# bmp180.net
KiCad netlist of a schematic drawn in EAGLE
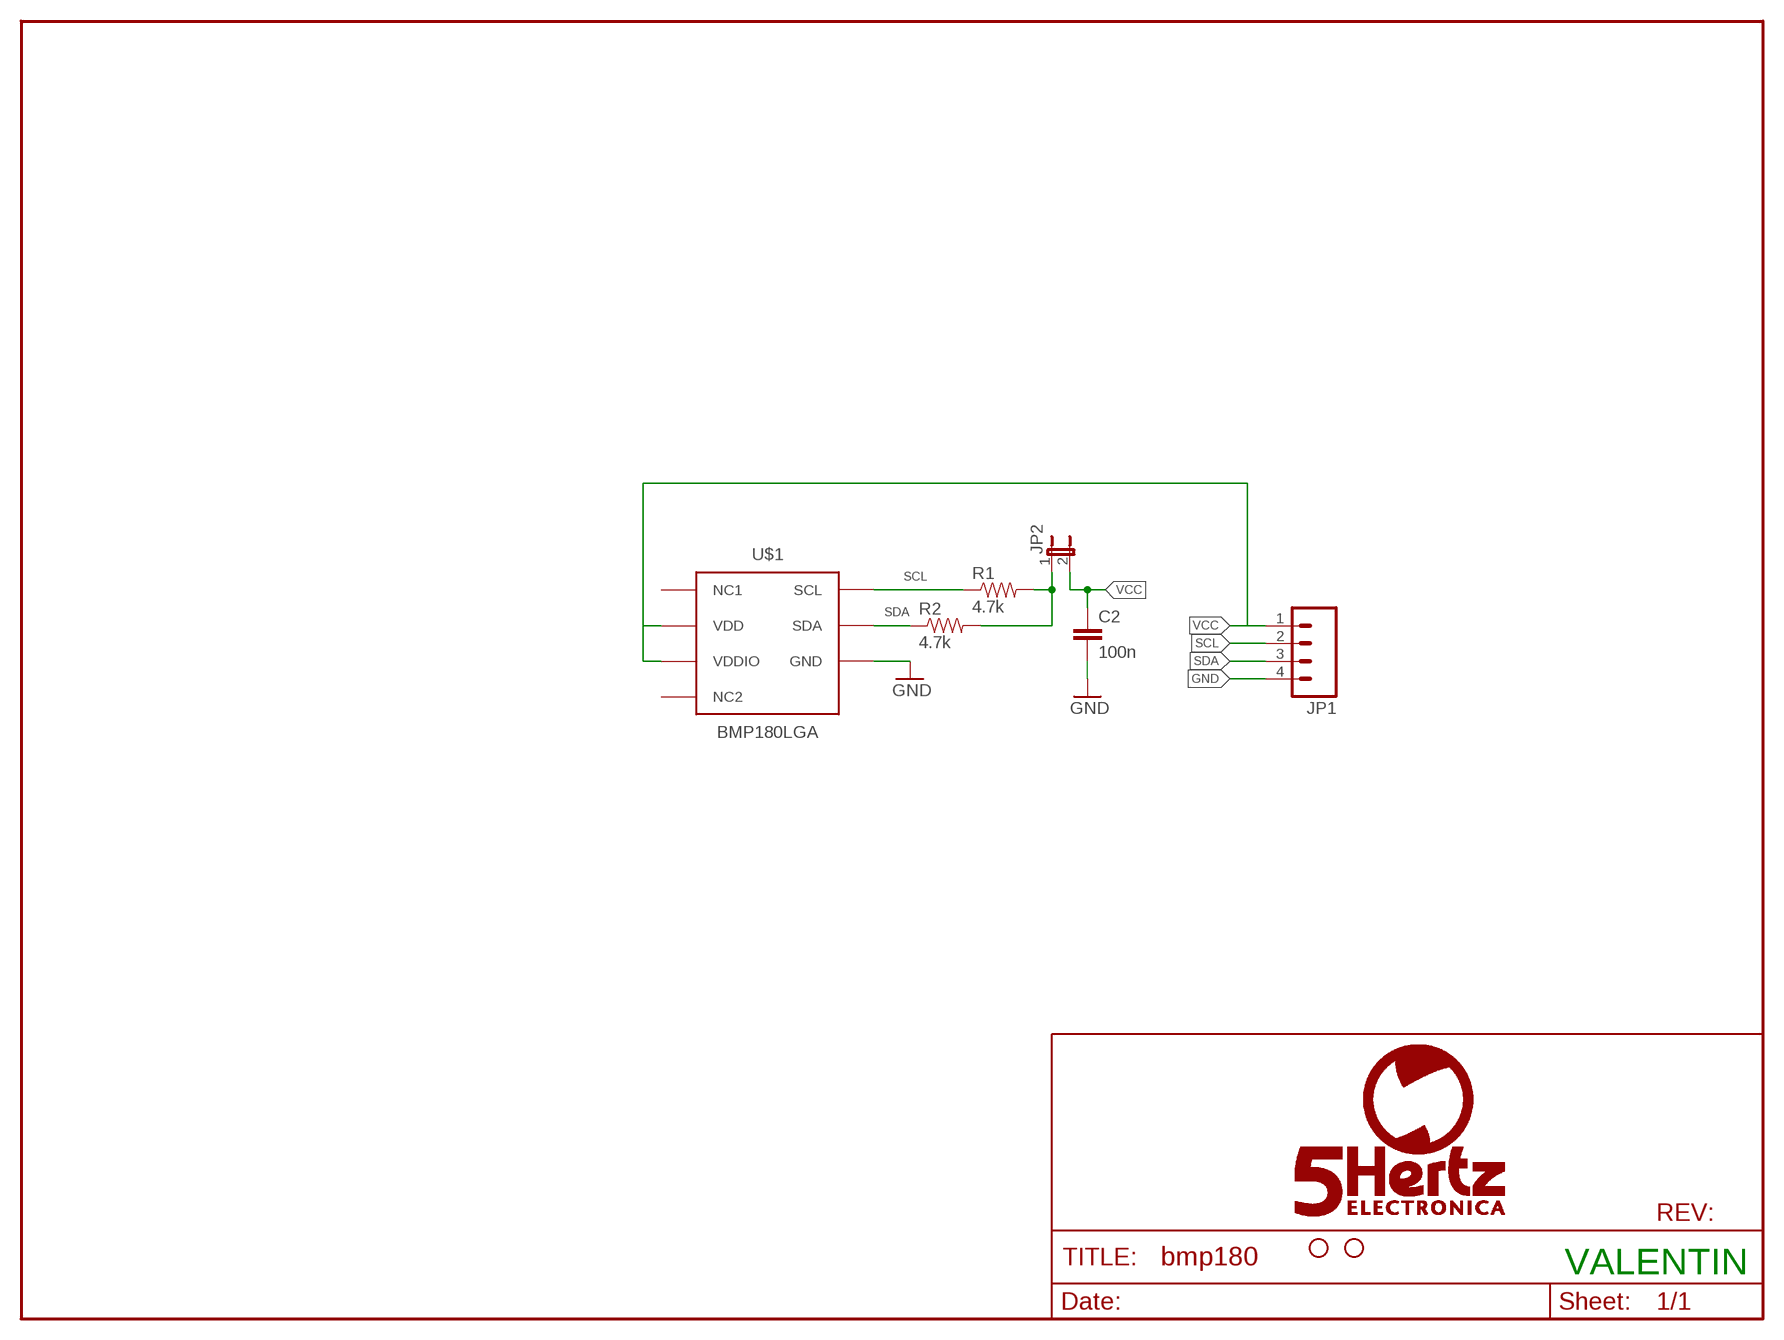
[diagram p0: schematic, sheet 1]

(export (version "E")
  (design (tool "Eeschema 10.0.6"))
  (components
    (comp (ref "C2")
      (value "100n")
      (footprint "eagle-import:0603-CAP")
      (libsource (lib "eagle-import") (part "CAP0603-CAP"))
    )
    (comp (ref "JP1")
      (value "M04PTH")
      (footprint "eagle-import:1X04")
      (libsource (lib "eagle-import") (part "M04PTH"))
    )
    (comp (ref "JP2")
      (value "JUMPER-2SMD-NO")
      (footprint "eagle-import:SJ_2S-NO")
      (libsource (lib "eagle-import") (part "JUMPER-2SMD-NO"))
    )
    (comp (ref "JP3")
      (value "STAND-OFFTIGHT")
      (footprint "eagle-import:STAND-OFF-TIGHT")
      (libsource (lib "eagle-import") (part "STAND-OFFTIGHT"))
    )
    (comp (ref "JP4")
      (value "STAND-OFFTIGHT")
      (footprint "eagle-import:STAND-OFF-TIGHT")
      (libsource (lib "eagle-import") (part "STAND-OFFTIGHT"))
    )
    (comp (ref "R1")
      (value "4.7k")
      (footprint "eagle-import:0603-RES")
      (libsource (lib "eagle-import") (part "RESISTOR0603-RES"))
    )
    (comp (ref "R2")
      (value "4.7k")
      (footprint "eagle-import:0603-RES")
      (libsource (lib "eagle-import") (part "RESISTOR0603-RES"))
    )
    (comp (ref "U$1")
      (value "BMP180LGA")
      (footprint "eagle-import:BMP180_LGA")
      (libsource (lib "eagle-import") (part "BMP180LGA"))
    )
  )
  (nets
    (net (code "1") (name "GND") (class "Default")
      (node (ref "C2") (pin "2") (pinfunction "2_2") (pintype "passive"))
      (node (ref "JP1") (pin "4") (pinfunction "4_4") (pintype "passive"))
      (node (ref "U$1") (pin "P$7") (pinfunction "GND_P$7") (pintype "bidirectional"))
    )
    (net (code "2") (name "Net-(JP2-Pad1)") (class "Default")
      (node (ref "JP2") (pin "1") (pinfunction "1_1") (pintype "passive"))
      (node (ref "R1") (pin "2") (pinfunction "2_2") (pintype "passive"))
      (node (ref "R2") (pin "2") (pinfunction "2_2") (pintype "passive"))
    )
    (net (code "3") (name "SCL") (class "Default")
      (node (ref "JP1") (pin "2") (pinfunction "2_2") (pintype "passive"))
      (node (ref "R1") (pin "1") (pinfunction "1_1") (pintype "passive"))
      (node (ref "U$1") (pin "P$5") (pinfunction "SCL_P$5") (pintype "bidirectional"))
    )
    (net (code "4") (name "SDA") (class "Default")
      (node (ref "JP1") (pin "3") (pinfunction "3_3") (pintype "passive"))
      (node (ref "R2") (pin "1") (pinfunction "1_1") (pintype "passive"))
      (node (ref "U$1") (pin "P$6") (pinfunction "SDA_P$6") (pintype "bidirectional"))
    )
    (net (code "5") (name "VCC") (class "Default")
      (node (ref "C2") (pin "1") (pinfunction "1_1") (pintype "passive"))
      (node (ref "JP1") (pin "1") (pinfunction "1_1") (pintype "passive"))
      (node (ref "JP2") (pin "2") (pinfunction "2_2") (pintype "passive"))
      (node (ref "U$1") (pin "P$2") (pinfunction "VDD_P$2") (pintype "bidirectional"))
      (node (ref "U$1") (pin "P$3") (pinfunction "VDDIO_P$3") (pintype "bidirectional"))
    )
    (net (code "6") (name "unconnected-(U$1-NC1-PadP$1)") (class "Default")
      (node (ref "U$1") (pin "P$1") (pinfunction "NC1_P$1") (pintype "bidirectional"))
    )
    (net (code "7") (name "unconnected-(U$1-NC2-PadP$4)") (class "Default")
      (node (ref "U$1") (pin "P$4") (pinfunction "NC2_P$4") (pintype "bidirectional"))
    )
  )
)
